# PowerRouting.net
KiCad netlist of a schematic drawn in Altium Designer
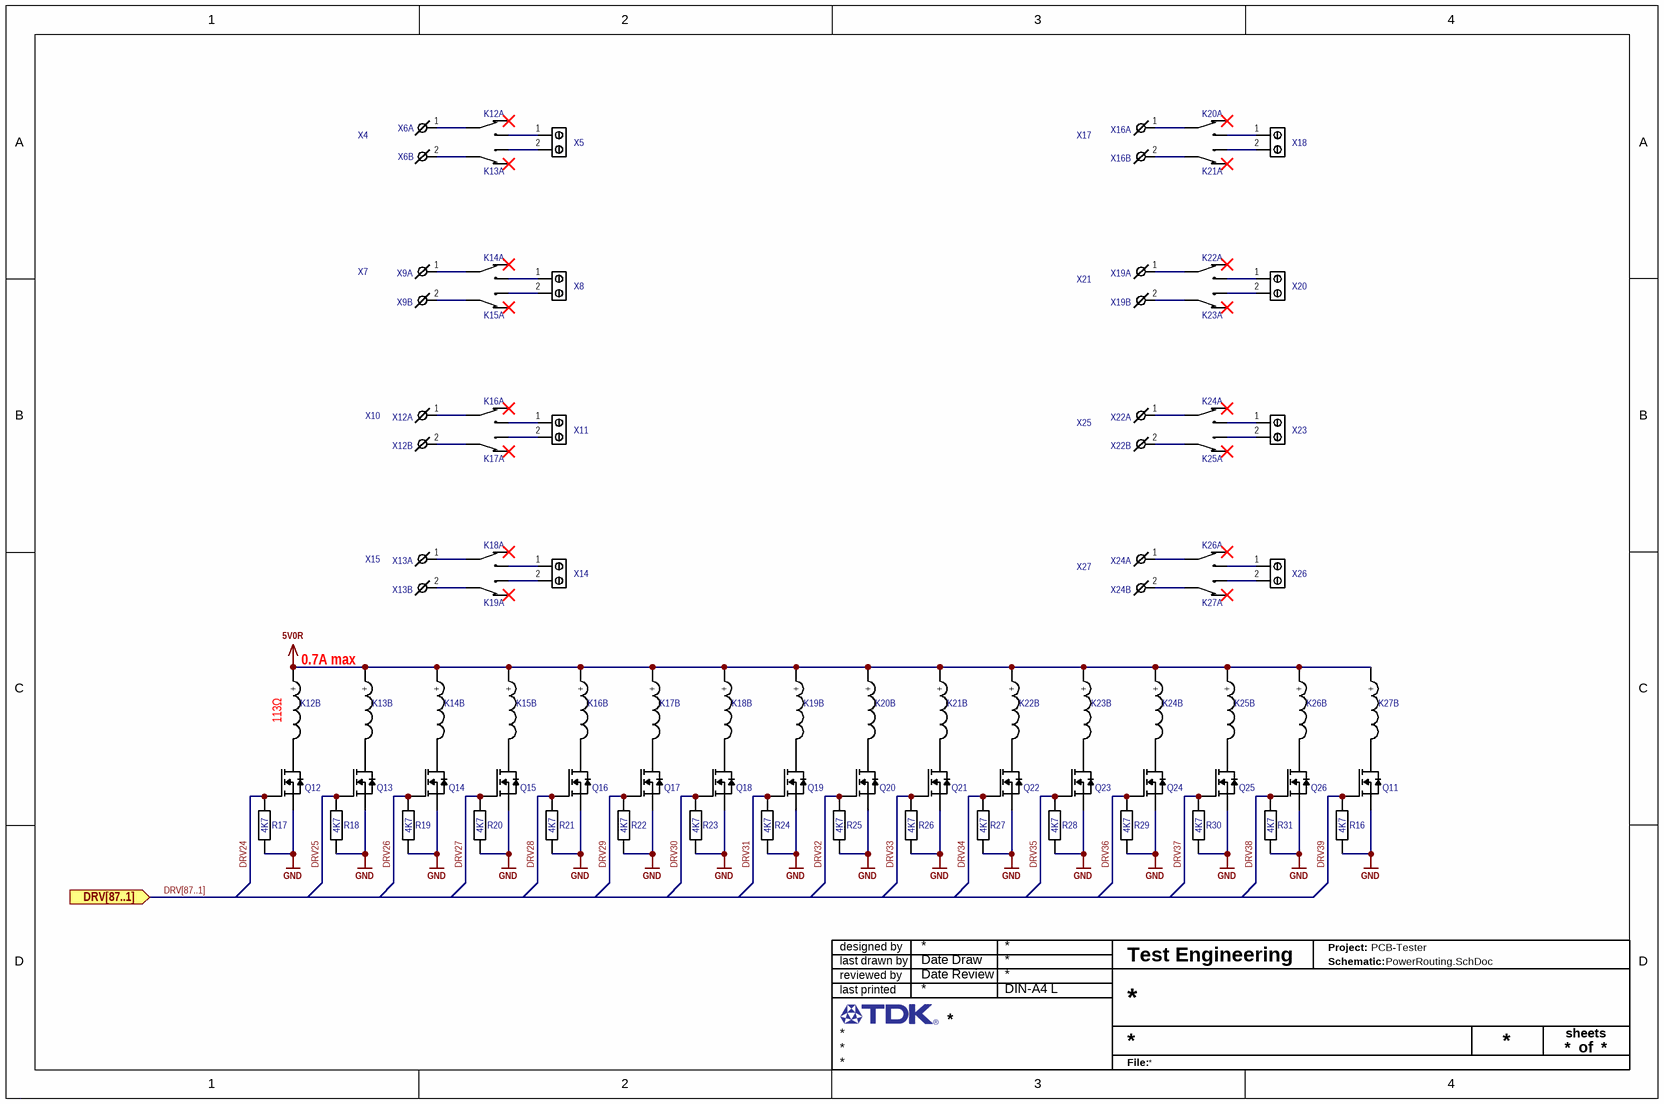
[diagram p0: PowerRouting.SchDoc]

(export (version "E")
  (design (tool "Eeschema 10.0.6"))
  (components
    (comp (ref "K12")
      (value "K")
      (footprint "HF118F005-1ZS1")
      (description "5V Power Relay, switch over")
      (fields
        (field (name "02. DISTRIBUTOR PART NUMBER") "176-2821")
        (field (name "07. MANUFACTURER  PART NUMBER") "HF118F/005-1ZS1T(136)")
        (field (name "COIL RESISTANCE") "113Ω")
        (field (name "13. CREATED DATE/NAME") "AUG2018/Hören")
      )
      (libsource (lib "chickenfood") (part "HF118F005-1ZS1"))
    )
    (comp (ref "K13")
      (value "K")
      (footprint "HF118F005-1ZS1")
      (description "5V Power Relay, switch over")
      (fields
        (field (name "02. DISTRIBUTOR PART NUMBER") "176-2821")
        (field (name "07. MANUFACTURER  PART NUMBER") "HF118F/005-1ZS1T(136)")
        (field (name "13. CREATED DATE/NAME") "AUG2018/Hören")
      )
      (libsource (lib "chickenfood") (part "HF118F005-1ZS1"))
    )
    (comp (ref "K14")
      (value "K")
      (footprint "HF118F005-1ZS1")
      (description "5V Power Relay, switch over")
      (fields
        (field (name "02. DISTRIBUTOR PART NUMBER") "176-2821")
        (field (name "07. MANUFACTURER  PART NUMBER") "HF118F/005-1ZS1T(136)")
        (field (name "13. CREATED DATE/NAME") "AUG2018/Hören")
      )
      (libsource (lib "chickenfood") (part "HF118F005-1ZS1"))
    )
    (comp (ref "K15")
      (value "K")
      (footprint "HF118F005-1ZS1")
      (description "5V Power Relay, switch over")
      (fields
        (field (name "02. DISTRIBUTOR PART NUMBER") "176-2821")
        (field (name "07. MANUFACTURER  PART NUMBER") "HF118F/005-1ZS1T(136)")
        (field (name "13. CREATED DATE/NAME") "AUG2018/Hören")
      )
      (libsource (lib "") (part "HF118F005-1ZS1_1"))
    )
    (comp (ref "K16")
      (value "K")
      (footprint "HF118F005-1ZS1")
      (description "5V Power Relay, switch over")
      (fields
        (field (name "02. DISTRIBUTOR PART NUMBER") "176-2821")
        (field (name "07. MANUFACTURER  PART NUMBER") "HF118F/005-1ZS1T(136)")
        (field (name "13. CREATED DATE/NAME") "AUG2018/Hören")
      )
      (libsource (lib "chickenfood") (part "HF118F005-1ZS1"))
    )
    (comp (ref "K17")
      (value "K")
      (footprint "HF118F005-1ZS1")
      (description "5V Power Relay, switch over")
      (fields
        (field (name "02. DISTRIBUTOR PART NUMBER") "176-2821")
        (field (name "07. MANUFACTURER  PART NUMBER") "HF118F/005-1ZS1T(136)")
        (field (name "13. CREATED DATE/NAME") "AUG2018/Hören")
      )
      (libsource (lib "chickenfood") (part "HF118F005-1ZS1"))
    )
    (comp (ref "K18")
      (value "K")
      (footprint "HF118F005-1ZS1")
      (description "5V Power Relay, switch over")
      (fields
        (field (name "02. DISTRIBUTOR PART NUMBER") "176-2821")
        (field (name "07. MANUFACTURER  PART NUMBER") "HF118F/005-1ZS1T(136)")
        (field (name "13. CREATED DATE/NAME") "AUG2018/Hören")
      )
      (libsource (lib "chickenfood") (part "HF118F005-1ZS1"))
    )
    (comp (ref "K19")
      (value "K")
      (footprint "HF118F005-1ZS1")
      (description "5V Power Relay, switch over")
      (fields
        (field (name "02. DISTRIBUTOR PART NUMBER") "176-2821")
        (field (name "07. MANUFACTURER  PART NUMBER") "HF118F/005-1ZS1T(136)")
        (field (name "13. CREATED DATE/NAME") "AUG2018/Hören")
      )
      (libsource (lib "chickenfood") (part "HF118F005-1ZS1"))
    )
    (comp (ref "K20")
      (value "K")
      (footprint "HF118F005-1ZS1")
      (description "5V Power Relay, switch over")
      (fields
        (field (name "02. DISTRIBUTOR PART NUMBER") "176-2821")
        (field (name "07. MANUFACTURER  PART NUMBER") "HF118F/005-1ZS1T(136)")
        (field (name "13. CREATED DATE/NAME") "AUG2018/Hören")
      )
      (libsource (lib "chickenfood") (part "HF118F005-1ZS1"))
    )
    (comp (ref "K21")
      (value "K")
      (footprint "HF118F005-1ZS1")
      (description "5V Power Relay, switch over")
      (fields
        (field (name "02. DISTRIBUTOR PART NUMBER") "176-2821")
        (field (name "07. MANUFACTURER  PART NUMBER") "HF118F/005-1ZS1T(136)")
        (field (name "13. CREATED DATE/NAME") "AUG2018/Hören")
      )
      (libsource (lib "") (part "HF118F005-1ZS1_1"))
    )
    (comp (ref "K22")
      (value "K")
      (footprint "HF118F005-1ZS1")
      (description "5V Power Relay, switch over")
      (fields
        (field (name "02. DISTRIBUTOR PART NUMBER") "176-2821")
        (field (name "07. MANUFACTURER  PART NUMBER") "HF118F/005-1ZS1T(136)")
        (field (name "13. CREATED DATE/NAME") "AUG2018/Hören")
      )
      (libsource (lib "chickenfood") (part "HF118F005-1ZS1"))
    )
    (comp (ref "K23")
      (value "K")
      (footprint "HF118F005-1ZS1")
      (description "5V Power Relay, switch over")
      (fields
        (field (name "02. DISTRIBUTOR PART NUMBER") "176-2821")
        (field (name "07. MANUFACTURER  PART NUMBER") "HF118F/005-1ZS1T(136)")
        (field (name "13. CREATED DATE/NAME") "AUG2018/Hören")
      )
      (libsource (lib "") (part "HF118F005-1ZS1_1"))
    )
    (comp (ref "K24")
      (value "K")
      (footprint "HF118F005-1ZS1")
      (description "5V Power Relay, switch over")
      (fields
        (field (name "02. DISTRIBUTOR PART NUMBER") "176-2821")
        (field (name "07. MANUFACTURER  PART NUMBER") "HF118F/005-1ZS1T(136)")
        (field (name "13. CREATED DATE/NAME") "AUG2018/Hören")
      )
      (libsource (lib "chickenfood") (part "HF118F005-1ZS1"))
    )
    (comp (ref "K25")
      (value "K")
      (footprint "HF118F005-1ZS1")
      (description "5V Power Relay, switch over")
      (fields
        (field (name "02. DISTRIBUTOR PART NUMBER") "176-2821")
        (field (name "07. MANUFACTURER  PART NUMBER") "HF118F/005-1ZS1T(136)")
        (field (name "13. CREATED DATE/NAME") "AUG2018/Hören")
      )
      (libsource (lib "chickenfood") (part "HF118F005-1ZS1"))
    )
    (comp (ref "K26")
      (value "K")
      (footprint "HF118F005-1ZS1")
      (description "5V Power Relay, switch over")
      (fields
        (field (name "02. DISTRIBUTOR PART NUMBER") "176-2821")
        (field (name "07. MANUFACTURER  PART NUMBER") "HF118F/005-1ZS1T(136)")
        (field (name "13. CREATED DATE/NAME") "AUG2018/Hören")
      )
      (libsource (lib "chickenfood") (part "HF118F005-1ZS1"))
    )
    (comp (ref "K27")
      (value "K")
      (footprint "HF118F005-1ZS1")
      (description "5V Power Relay, switch over")
      (fields
        (field (name "02. DISTRIBUTOR PART NUMBER") "176-2821")
        (field (name "07. MANUFACTURER  PART NUMBER") "HF118F/005-1ZS1T(136)")
        (field (name "13. CREATED DATE/NAME") "AUG2018/Hören")
      )
      (libsource (lib "") (part "HF118F005-1ZS1_1"))
    )
    (comp (ref "Q11")
      (value "Q")
      (footprint "SOT23-3")
      (description "MOSFET N-CH 25V 680MA SOT-23")
      (fields
        (field (name "02. DISTRIBUTOR PART NUMBER") "FDV303NDKR-ND")
        (field (name "07. MANUFACTURER  PART NUMBER") "FDV303N")
        (field (name "13. CREATED DATE/NAME") "AUG 2018 / Hören")
      )
      (libsource (lib "SCT8-Board1") (part "FDV303N"))
    )
    (comp (ref "Q12")
      (value "Q")
      (footprint "SOT23-3")
      (description "MOSFET N-CH 25V 680MA SOT-23")
      (fields
        (field (name "02. DISTRIBUTOR PART NUMBER") "FDV303NDKR-ND")
        (field (name "07. MANUFACTURER  PART NUMBER") "FDV303N")
        (field (name "13. CREATED DATE/NAME") "AUG 2018 / Hören")
      )
      (libsource (lib "SCT8-Board1") (part "FDV303N"))
    )
    (comp (ref "Q13")
      (value "Q")
      (footprint "SOT23-3")
      (description "MOSFET N-CH 25V 680MA SOT-23")
      (fields
        (field (name "02. DISTRIBUTOR PART NUMBER") "FDV303NDKR-ND")
        (field (name "07. MANUFACTURER  PART NUMBER") "FDV303N")
        (field (name "13. CREATED DATE/NAME") "AUG 2018 / Hören")
      )
      (libsource (lib "SCT8-Board1") (part "FDV303N"))
    )
    (comp (ref "Q14")
      (value "Q")
      (footprint "SOT23-3")
      (description "MOSFET N-CH 25V 680MA SOT-23")
      (fields
        (field (name "02. DISTRIBUTOR PART NUMBER") "FDV303NDKR-ND")
        (field (name "07. MANUFACTURER  PART NUMBER") "FDV303N")
        (field (name "13. CREATED DATE/NAME") "AUG 2018 / Hören")
      )
      (libsource (lib "SCT8-Board1") (part "FDV303N"))
    )
    (comp (ref "Q15")
      (value "Q")
      (footprint "SOT23-3")
      (description "MOSFET N-CH 25V 680MA SOT-23")
      (fields
        (field (name "02. DISTRIBUTOR PART NUMBER") "FDV303NDKR-ND")
        (field (name "07. MANUFACTURER  PART NUMBER") "FDV303N")
        (field (name "13. CREATED DATE/NAME") "AUG 2018 / Hören")
      )
      (libsource (lib "SCT8-Board1") (part "FDV303N"))
    )
    (comp (ref "Q16")
      (value "Q")
      (footprint "SOT23-3")
      (description "MOSFET N-CH 25V 680MA SOT-23")
      (fields
        (field (name "02. DISTRIBUTOR PART NUMBER") "FDV303NDKR-ND")
        (field (name "07. MANUFACTURER  PART NUMBER") "FDV303N")
        (field (name "13. CREATED DATE/NAME") "AUG 2018 / Hören")
      )
      (libsource (lib "SCT8-Board1") (part "FDV303N"))
    )
    (comp (ref "Q17")
      (value "Q")
      (footprint "SOT23-3")
      (description "MOSFET N-CH 25V 680MA SOT-23")
      (fields
        (field (name "02. DISTRIBUTOR PART NUMBER") "FDV303NDKR-ND")
        (field (name "07. MANUFACTURER  PART NUMBER") "FDV303N")
        (field (name "13. CREATED DATE/NAME") "AUG 2018 / Hören")
      )
      (libsource (lib "SCT8-Board1") (part "FDV303N"))
    )
    (comp (ref "Q18")
      (value "Q")
      (footprint "SOT23-3")
      (description "MOSFET N-CH 25V 680MA SOT-23")
      (fields
        (field (name "02. DISTRIBUTOR PART NUMBER") "FDV303NDKR-ND")
        (field (name "07. MANUFACTURER  PART NUMBER") "FDV303N")
        (field (name "13. CREATED DATE/NAME") "AUG 2018 / Hören")
      )
      (libsource (lib "SCT8-Board1") (part "FDV303N"))
    )
    (comp (ref "Q19")
      (value "Q")
      (footprint "SOT23-3")
      (description "MOSFET N-CH 25V 680MA SOT-23")
      (fields
        (field (name "02. DISTRIBUTOR PART NUMBER") "FDV303NDKR-ND")
        (field (name "07. MANUFACTURER  PART NUMBER") "FDV303N")
        (field (name "13. CREATED DATE/NAME") "AUG 2018 / Hören")
      )
      (libsource (lib "SCT8-Board1") (part "FDV303N"))
    )
    (comp (ref "Q20")
      (value "Q")
      (footprint "SOT23-3")
      (description "MOSFET N-CH 25V 680MA SOT-23")
      (fields
        (field (name "02. DISTRIBUTOR PART NUMBER") "FDV303NDKR-ND")
        (field (name "07. MANUFACTURER  PART NUMBER") "FDV303N")
        (field (name "13. CREATED DATE/NAME") "AUG 2018 / Hören")
      )
      (libsource (lib "SCT8-Board1") (part "FDV303N"))
    )
    (comp (ref "Q21")
      (value "Q")
      (footprint "SOT23-3")
      (description "MOSFET N-CH 25V 680MA SOT-23")
      (fields
        (field (name "02. DISTRIBUTOR PART NUMBER") "FDV303NDKR-ND")
        (field (name "07. MANUFACTURER  PART NUMBER") "FDV303N")
        (field (name "13. CREATED DATE/NAME") "AUG 2018 / Hören")
      )
      (libsource (lib "SCT8-Board1") (part "FDV303N"))
    )
    (comp (ref "Q22")
      (value "Q")
      (footprint "SOT23-3")
      (description "MOSFET N-CH 25V 680MA SOT-23")
      (fields
        (field (name "02. DISTRIBUTOR PART NUMBER") "FDV303NDKR-ND")
        (field (name "07. MANUFACTURER  PART NUMBER") "FDV303N")
        (field (name "13. CREATED DATE/NAME") "AUG 2018 / Hören")
      )
      (libsource (lib "SCT8-Board1") (part "FDV303N"))
    )
    (comp (ref "Q23")
      (value "Q")
      (footprint "SOT23-3")
      (description "MOSFET N-CH 25V 680MA SOT-23")
      (fields
        (field (name "02. DISTRIBUTOR PART NUMBER") "FDV303NDKR-ND")
        (field (name "07. MANUFACTURER  PART NUMBER") "FDV303N")
        (field (name "13. CREATED DATE/NAME") "AUG 2018 / Hören")
      )
      (libsource (lib "SCT8-Board1") (part "FDV303N"))
    )
    (comp (ref "Q24")
      (value "Q")
      (footprint "SOT23-3")
      (description "MOSFET N-CH 25V 680MA SOT-23")
      (fields
        (field (name "02. DISTRIBUTOR PART NUMBER") "FDV303NDKR-ND")
        (field (name "07. MANUFACTURER  PART NUMBER") "FDV303N")
        (field (name "13. CREATED DATE/NAME") "AUG 2018 / Hören")
      )
      (libsource (lib "SCT8-Board1") (part "FDV303N"))
    )
    (comp (ref "Q25")
      (value "Q")
      (footprint "SOT23-3")
      (description "MOSFET N-CH 25V 680MA SOT-23")
      (fields
        (field (name "02. DISTRIBUTOR PART NUMBER") "FDV303NDKR-ND")
        (field (name "07. MANUFACTURER  PART NUMBER") "FDV303N")
        (field (name "13. CREATED DATE/NAME") "AUG 2018 / Hören")
      )
      (libsource (lib "SCT8-Board1") (part "FDV303N"))
    )
    (comp (ref "Q26")
      (value "Q")
      (footprint "SOT23-3")
      (description "MOSFET N-CH 25V 680MA SOT-23")
      (fields
        (field (name "02. DISTRIBUTOR PART NUMBER") "FDV303NDKR-ND")
        (field (name "07. MANUFACTURER  PART NUMBER") "FDV303N")
        (field (name "13. CREATED DATE/NAME") "AUG 2018 / Hören")
      )
      (libsource (lib "SCT8-Board1") (part "FDV303N"))
    )
    (comp (ref "R16")
      (value "4K7")
      (footprint "R0402 Reflow")
      (description "Resistor")
      (fields
        (field (name "TOLERANCE") "±1%")
        (field (name "Comment") "R")
        (field (name "13. CREATED DATE/NAME") "AUG2018/Hören")
      )
      (libsource (lib "chickenfood") (part "R"))
    )
    (comp (ref "R17")
      (value "4K7")
      (footprint "R0402 Reflow")
      (description "Resistor")
      (fields
        (field (name "TOLERANCE") "±1%")
        (field (name "Comment") "R")
        (field (name "13. CREATED DATE/NAME") "AUG2018/Hören")
      )
      (libsource (lib "chickenfood") (part "R"))
    )
    (comp (ref "R18")
      (value "4K7")
      (footprint "R0402 Reflow")
      (description "Resistor")
      (fields
        (field (name "TOLERANCE") "±1%")
        (field (name "Comment") "R")
        (field (name "13. CREATED DATE/NAME") "AUG2018/Hören")
      )
      (libsource (lib "chickenfood") (part "R"))
    )
    (comp (ref "R19")
      (value "4K7")
      (footprint "R0402 Reflow")
      (description "Resistor")
      (fields
        (field (name "TOLERANCE") "±1%")
        (field (name "Comment") "R")
        (field (name "13. CREATED DATE/NAME") "AUG2018/Hören")
      )
      (libsource (lib "chickenfood") (part "R"))
    )
    (comp (ref "R20")
      (value "4K7")
      (footprint "R0402 Reflow")
      (description "Resistor")
      (fields
        (field (name "TOLERANCE") "±1%")
        (field (name "Comment") "R")
        (field (name "13. CREATED DATE/NAME") "AUG2018/Hören")
      )
      (libsource (lib "chickenfood") (part "R"))
    )
    (comp (ref "R21")
      (value "4K7")
      (footprint "R0402 Reflow")
      (description "Resistor")
      (fields
        (field (name "TOLERANCE") "±1%")
        (field (name "Comment") "R")
        (field (name "13. CREATED DATE/NAME") "AUG2018/Hören")
      )
      (libsource (lib "chickenfood") (part "R"))
    )
    (comp (ref "R22")
      (value "4K7")
      (footprint "R0402 Reflow")
      (description "Resistor")
      (fields
        (field (name "TOLERANCE") "±1%")
        (field (name "Comment") "R")
        (field (name "13. CREATED DATE/NAME") "AUG2018/Hören")
      )
      (libsource (lib "chickenfood") (part "R"))
    )
    (comp (ref "R23")
      (value "4K7")
      (footprint "R0402 Reflow")
      (description "Resistor")
      (fields
        (field (name "TOLERANCE") "±1%")
        (field (name "Comment") "R")
        (field (name "13. CREATED DATE/NAME") "AUG2018/Hören")
      )
      (libsource (lib "chickenfood") (part "R"))
    )
    (comp (ref "R24")
      (value "4K7")
      (footprint "R0402 Reflow")
      (description "Resistor")
      (fields
        (field (name "TOLERANCE") "±1%")
        (field (name "Comment") "R")
        (field (name "13. CREATED DATE/NAME") "AUG2018/Hören")
      )
      (libsource (lib "chickenfood") (part "R"))
    )
    (comp (ref "R25")
      (value "4K7")
      (footprint "R0402 Reflow")
      (description "Resistor")
      (fields
        (field (name "TOLERANCE") "±1%")
        (field (name "Comment") "R")
        (field (name "13. CREATED DATE/NAME") "AUG2018/Hören")
      )
      (libsource (lib "chickenfood") (part "R"))
    )
    (comp (ref "R26")
      (value "4K7")
      (footprint "R0402 Reflow")
      (description "Resistor")
      (fields
        (field (name "TOLERANCE") "±1%")
        (field (name "Comment") "R")
        (field (name "13. CREATED DATE/NAME") "AUG2018/Hören")
      )
      (libsource (lib "chickenfood") (part "R"))
    )
    (comp (ref "R27")
      (value "4K7")
      (footprint "R0402 Reflow")
      (description "Resistor")
      (fields
        (field (name "TOLERANCE") "±1%")
        (field (name "Comment") "R")
        (field (name "13. CREATED DATE/NAME") "AUG2018/Hören")
      )
      (libsource (lib "chickenfood") (part "R"))
    )
    (comp (ref "R28")
      (value "4K7")
      (footprint "R0402 Reflow")
      (description "Resistor")
      (fields
        (field (name "TOLERANCE") "±1%")
        (field (name "Comment") "R")
        (field (name "13. CREATED DATE/NAME") "AUG2018/Hören")
      )
      (libsource (lib "chickenfood") (part "R"))
    )
    (comp (ref "R29")
      (value "4K7")
      (footprint "R0402 Reflow")
      (description "Resistor")
      (fields
        (field (name "TOLERANCE") "±1%")
        (field (name "Comment") "R")
        (field (name "13. CREATED DATE/NAME") "AUG2018/Hören")
      )
      (libsource (lib "chickenfood") (part "R"))
    )
    (comp (ref "R30")
      (value "4K7")
      (footprint "R0402 Reflow")
      (description "Resistor")
      (fields
        (field (name "TOLERANCE") "±1%")
        (field (name "Comment") "R")
        (field (name "13. CREATED DATE/NAME") "AUG2018/Hören")
      )
      (libsource (lib "chickenfood") (part "R"))
    )
    (comp (ref "R31")
      (value "4K7")
      (footprint "R0402 Reflow")
      (description "Resistor")
      (fields
        (field (name "TOLERANCE") "±1%")
        (field (name "Comment") "R")
        (field (name "13. CREATED DATE/NAME") "AUG2018/Hören")
      )
      (libsource (lib "chickenfood") (part "R"))
    )
    (comp (ref "X4")
      (value "X")
      (footprint "691352710002")
      (description "TERM BLOCK PLUG 2POS STR 5MM")
      (fields (field (name "13. CREATED DATE/NAME") "??? / Hören"))
      (libsource (lib "Connectors") (part "691352710002"))
    )
    (comp (ref "X5")
      (value "X")
      (footprint "1731721")
      (description "TERM BLK 2P SIDE ENT 7.62MM PCB")
      (fields
        (field (name "02. DISTRIBUTOR PART NUMBER") "277-5849-ND")
        (field (name "07. MANUFACTURER  PART NUMBER") "1731721")
        (field (name "13. CREATED DATE/NAME") "JAN 2019 / Hören")
      )
      (libsource (lib "Connectors") (part "1731721"))
    )
    (comp (ref "X6")
      (value "X")
      (footprint "691312710002")
      (description "TERM BLOCK HDR 2POS 90DEG 5MM")
      (fields
        (field (name "02. DISTRIBUTOR PART NUMBER") "732-2805-ND")
        (field (name "07. MANUFACTURER  PART NUMBER") "691312710002")
        (field (name "13. CREATED DATE/NAME") "??? / Hören")
      )
      (libsource (lib "Connectors") (part "691312710002"))
    )
    (comp (ref "X7")
      (value "X")
      (footprint "691352710002")
      (description "TERM BLOCK PLUG 2POS STR 5MM")
      (fields (field (name "13. CREATED DATE/NAME") "??? / Hören"))
      (libsource (lib "Connectors") (part "691352710002"))
    )
    (comp (ref "X8")
      (value "X")
      (footprint "1731721")
      (description "TERM BLK 2P SIDE ENT 7.62MM PCB")
      (fields
        (field (name "02. DISTRIBUTOR PART NUMBER") "277-5849-ND")
        (field (name "07. MANUFACTURER  PART NUMBER") "1731721")
        (field (name "13. CREATED DATE/NAME") "JAN 2019 / Hören")
      )
      (libsource (lib "Connectors") (part "1731721"))
    )
    (comp (ref "X9")
      (value "X")
      (footprint "691312710002")
      (description "TERM BLOCK HDR 2POS 90DEG 5MM")
      (fields
        (field (name "02. DISTRIBUTOR PART NUMBER") "732-2805-ND")
        (field (name "07. MANUFACTURER  PART NUMBER") "691312710002")
        (field (name "13. CREATED DATE/NAME") "??? / Hören")
      )
      (libsource (lib "Connectors") (part "691312710002"))
    )
    (comp (ref "X10")
      (value "X")
      (footprint "691352710002")
      (description "TERM BLOCK PLUG 2POS STR 5MM")
      (fields (field (name "13. CREATED DATE/NAME") "??? / Hören"))
      (libsource (lib "Connectors") (part "691352710002"))
    )
    (comp (ref "X11")
      (value "X")
      (footprint "1731721")
      (description "TERM BLK 2P SIDE ENT 7.62MM PCB")
      (fields
        (field (name "02. DISTRIBUTOR PART NUMBER") "277-5849-ND")
        (field (name "07. MANUFACTURER  PART NUMBER") "1731721")
        (field (name "13. CREATED DATE/NAME") "JAN 2019 / Hören")
      )
      (libsource (lib "Connectors") (part "1731721"))
    )
    (comp (ref "X12")
      (value "X")
      (footprint "691312710002")
      (description "TERM BLOCK HDR 2POS 90DEG 5MM")
      (fields
        (field (name "02. DISTRIBUTOR PART NUMBER") "732-2805-ND")
        (field (name "07. MANUFACTURER  PART NUMBER") "691312710002")
        (field (name "13. CREATED DATE/NAME") "??? / Hören")
      )
      (libsource (lib "Connectors") (part "691312710002"))
    )
    (comp (ref "X13")
      (value "X")
      (footprint "691312710002")
      (description "TERM BLOCK HDR 2POS 90DEG 5MM")
      (fields
        (field (name "02. DISTRIBUTOR PART NUMBER") "732-2805-ND")
        (field (name "07. MANUFACTURER  PART NUMBER") "691312710002")
        (field (name "13. CREATED DATE/NAME") "??? / Hören")
      )
      (libsource (lib "Connectors") (part "691312710002"))
    )
    (comp (ref "X14")
      (value "X")
      (footprint "1731721")
      (description "TERM BLK 2P SIDE ENT 7.62MM PCB")
      (fields
        (field (name "02. DISTRIBUTOR PART NUMBER") "277-5849-ND")
        (field (name "07. MANUFACTURER  PART NUMBER") "1731721")
        (field (name "13. CREATED DATE/NAME") "JAN 2019 / Hören")
      )
      (libsource (lib "Connectors") (part "1731721"))
    )
    (comp (ref "X15")
      (value "X")
      (footprint "691352710002")
      (description "TERM BLOCK PLUG 2POS STR 5MM")
      (fields (field (name "13. CREATED DATE/NAME") "??? / Hören"))
      (libsource (lib "Connectors") (part "691352710002"))
    )
    (comp (ref "X16")
      (value "X")
      (footprint "691312710002")
      (description "TERM BLOCK HDR 2POS 90DEG 5MM")
      (fields
        (field (name "02. DISTRIBUTOR PART NUMBER") "732-2805-ND")
        (field (name "07. MANUFACTURER  PART NUMBER") "691312710002")
        (field (name "13. CREATED DATE/NAME") "??? / Hören")
      )
      (libsource (lib "Connectors") (part "691312710002"))
    )
    (comp (ref "X17")
      (value "X")
      (footprint "691352710002")
      (description "TERM BLOCK PLUG 2POS STR 5MM")
      (fields (field (name "13. CREATED DATE/NAME") "??? / Hören"))
      (libsource (lib "Connectors") (part "691352710002"))
    )
    (comp (ref "X18")
      (value "X")
      (footprint "1731721")
      (description "TERM BLK 2P SIDE ENT 7.62MM PCB")
      (fields
        (field (name "02. DISTRIBUTOR PART NUMBER") "277-5849-ND")
        (field (name "07. MANUFACTURER  PART NUMBER") "1731721")
        (field (name "13. CREATED DATE/NAME") "JAN 2019 / Hören")
      )
      (libsource (lib "Connectors") (part "1731721"))
    )
    (comp (ref "X19")
      (value "X")
      (footprint "691312710002")
      (description "TERM BLOCK HDR 2POS 90DEG 5MM")
      (fields
        (field (name "02. DISTRIBUTOR PART NUMBER") "732-2805-ND")
        (field (name "07. MANUFACTURER  PART NUMBER") "691312710002")
        (field (name "13. CREATED DATE/NAME") "??? / Hören")
      )
      (libsource (lib "Connectors") (part "691312710002"))
    )
    (comp (ref "X20")
      (value "X")
      (footprint "1731721")
      (description "TERM BLK 2P SIDE ENT 7.62MM PCB")
      (fields
        (field (name "02. DISTRIBUTOR PART NUMBER") "277-5849-ND")
        (field (name "07. MANUFACTURER  PART NUMBER") "1731721")
        (field (name "13. CREATED DATE/NAME") "JAN 2019 / Hören")
      )
      (libsource (lib "Connectors") (part "1731721"))
    )
    (comp (ref "X21")
      (value "X")
      (footprint "691352710002")
      (description "TERM BLOCK PLUG 2POS STR 5MM")
      (fields (field (name "13. CREATED DATE/NAME") "??? / Hören"))
      (libsource (lib "Connectors") (part "691352710002"))
    )
    (comp (ref "X22")
      (value "X")
      (footprint "691312710002")
      (description "TERM BLOCK HDR 2POS 90DEG 5MM")
      (fields
        (field (name "02. DISTRIBUTOR PART NUMBER") "732-2805-ND")
        (field (name "07. MANUFACTURER  PART NUMBER") "691312710002")
        (field (name "13. CREATED DATE/NAME") "??? / Hören")
      )
      (libsource (lib "Connectors") (part "691312710002"))
    )
    (comp (ref "X23")
      (value "X")
      (footprint "1731721")
      (description "TERM BLK 2P SIDE ENT 7.62MM PCB")
      (fields
        (field (name "02. DISTRIBUTOR PART NUMBER") "277-5849-ND")
        (field (name "07. MANUFACTURER  PART NUMBER") "1731721")
        (field (name "13. CREATED DATE/NAME") "JAN 2019 / Hören")
      )
      (libsource (lib "Connectors") (part "1731721"))
    )
    (comp (ref "X24")
      (value "X")
      (footprint "691312710002")
      (description "TERM BLOCK HDR 2POS 90DEG 5MM")
      (fields
        (field (name "02. DISTRIBUTOR PART NUMBER") "732-2805-ND")
        (field (name "07. MANUFACTURER  PART NUMBER") "691312710002")
        (field (name "13. CREATED DATE/NAME") "??? / Hören")
      )
      (libsource (lib "Connectors") (part "691312710002"))
    )
    (comp (ref "X25")
      (value "X")
      (footprint "691352710002")
      (description "TERM BLOCK PLUG 2POS STR 5MM")
      (fields (field (name "13. CREATED DATE/NAME") "??? / Hören"))
      (libsource (lib "Connectors") (part "691352710002"))
    )
    (comp (ref "X26")
      (value "X")
      (footprint "1731721")
      (description "TERM BLK 2P SIDE ENT 7.62MM PCB")
      (fields
        (field (name "02. DISTRIBUTOR PART NUMBER") "277-5849-ND")
        (field (name "07. MANUFACTURER  PART NUMBER") "1731721")
        (field (name "13. CREATED DATE/NAME") "JAN 2019 / Hören")
      )
      (libsource (lib "Connectors") (part "1731721"))
    )
    (comp (ref "X27")
      (value "X")
      (footprint "691352710002")
      (description "TERM BLOCK PLUG 2POS STR 5MM")
      (fields (field (name "13. CREATED DATE/NAME") "??? / Hören"))
      (libsource (lib "Connectors") (part "691352710002"))
    )
  )
  (nets
    (net (code "72") (name "/DRV24") (class "Default")
      (node (ref "Q12") (pin "1") (pinfunction "G_1") (pintype "passive"))
      (node (ref "R17") (pin "2") (pinfunction "2_2") (pintype "passive"))
    )
    (net (code "73") (name "/DRV25") (class "Default")
      (node (ref "Q13") (pin "1") (pinfunction "G_1") (pintype "passive"))
      (node (ref "R18") (pin "2") (pinfunction "2_2") (pintype "passive"))
    )
    (net (code "74") (name "/DRV26") (class "Default")
      (node (ref "Q14") (pin "1") (pinfunction "G_1") (pintype "passive"))
      (node (ref "R19") (pin "2") (pinfunction "2_2") (pintype "passive"))
    )
    (net (code "75") (name "/DRV27") (class "Default")
      (node (ref "Q15") (pin "1") (pinfunction "G_1") (pintype "passive"))
      (node (ref "R20") (pin "2") (pinfunction "2_2") (pintype "passive"))
    )
    (net (code "76") (name "/DRV28") (class "Default")
      (node (ref "Q16") (pin "1") (pinfunction "G_1") (pintype "passive"))
      (node (ref "R21") (pin "2") (pinfunction "2_2") (pintype "passive"))
    )
    (net (code "77") (name "/DRV29") (class "Default")
      (node (ref "Q17") (pin "1") (pinfunction "G_1") (pintype "passive"))
      (node (ref "R22") (pin "2") (pinfunction "2_2") (pintype "passive"))
    )
    (net (code "78") (name "/DRV30") (class "Default")
      (node (ref "Q18") (pin "1") (pinfunction "G_1") (pintype "passive"))
      (node (ref "R23") (pin "2") (pinfunction "2_2") (pintype "passive"))
    )
    (net (code "79") (name "/DRV31") (class "Default")
      (node (ref "Q19") (pin "1") (pinfunction "G_1") (pintype "passive"))
      (node (ref "R24") (pin "2") (pinfunction "2_2") (pintype "passive"))
    )
    (net (code "80") (name "/DRV32") (class "Default")
      (node (ref "Q20") (pin "1") (pinfunction "G_1") (pintype "passive"))
      (node (ref "R25") (pin "2") (pinfunction "2_2") (pintype "passive"))
    )
    (net (code "81") (name "/DRV33") (class "Default")
      (node (ref "Q21") (pin "1") (pinfunction "G_1") (pintype "passive"))
      (node (ref "R26") (pin "2") (pinfunction "2_2") (pintype "passive"))
    )
    (net (code "82") (name "/DRV34") (class "Default")
      (node (ref "Q22") (pin "1") (pinfunction "G_1") (pintype "passive"))
      (node (ref "R27") (pin "2") (pinfunction "2_2") (pintype "passive"))
    )
    (net (code "83") (name "/DRV35") (class "Default")
      (node (ref "Q23") (pin "1") (pinfunction "G_1") (pintype "passive"))
      (node (ref "R28") (pin "2") (pinfunction "2_2") (pintype "passive"))
    )
    (net (code "84") (name "/DRV36") (class "Default")
      (node (ref "Q24") (pin "1") (pinfunction "G_1") (pintype "passive"))
      (node (ref "R29") (pin "2") (pinfunction "2_2") (pintype "passive"))
    )
    (net (code "85") (name "/DRV37") (class "Default")
      (node (ref "Q25") (pin "1") (pinfunction "G_1") (pintype "passive"))
      (node (ref "R30") (pin "2") (pinfunction "2_2") (pintype "passive"))
    )
    (net (code "86") (name "/DRV38") (class "Default")
      (node (ref "Q26") (pin "1") (pinfunction "G_1") (pintype "passive"))
      (node (ref "R31") (pin "2") (pinfunction "2_2") (pintype "passive"))
    )
    (net (code "87") (name "/DRV39") (class "Default")
      (node (ref "Q11") (pin "1") (pinfunction "G_1") (pintype "passive"))
      (node (ref "R16") (pin "2") (pinfunction "2_2") (pintype "passive"))
    )
    (net (code "89") (name "5V0R") (class "Default")
      (node (ref "K12") (pin "1") (pinfunction "+_1") (pintype "passive"))
      (node (ref "K13") (pin "1") (pinfunction "+_1") (pintype "passive"))
      (node (ref "K14") (pin "1") (pinfunction "+_1") (pintype "passive"))
      (node (ref "K15") (pin "1") (pinfunction "+_1") (pintype "passive"))
      (node (ref "K16") (pin "1") (pinfunction "+_1") (pintype "passive"))
      (node (ref "K17") (pin "1") (pinfunction "+_1") (pintype "passive"))
      (node (ref "K18") (pin "1") (pinfunction "+_1") (pintype "passive"))
      (node (ref "K19") (pin "1") (pinfunction "+_1") (pintype "passive"))
      (node (ref "K20") (pin "1") (pinfunction "+_1") (pintype "passive"))
      (node (ref "K21") (pin "1") (pinfunction "+_1") (pintype "passive"))
      (node (ref "K22") (pin "1") (pinfunction "+_1") (pintype "passive"))
      (node (ref "K23") (pin "1") (pinfunction "+_1") (pintype "passive"))
      (node (ref "K24") (pin "1") (pinfunction "+_1") (pintype "passive"))
      (node (ref "K25") (pin "1") (pinfunction "+_1") (pintype "passive"))
      (node (ref "K26") (pin "1") (pinfunction "+_1") (pintype "passive"))
      (node (ref "K27") (pin "1") (pinfunction "+_1") (pintype "passive"))
    )
    (net (code "90") (name "GND") (class "Default")
      (node (ref "Q11") (pin "2") (pinfunction "S_2") (pintype "passive"))
      (node (ref "Q12") (pin "2") (pinfunction "S_2") (pintype "passive"))
      (node (ref "Q13") (pin "2") (pinfunction "S_2") (pintype "passive"))
      (node (ref "Q14") (pin "2") (pinfunction "S_2") (pintype "passive"))
      (node (ref "Q15") (pin "2") (pinfunction "S_2") (pintype "passive"))
      (node (ref "Q16") (pin "2") (pinfunction "S_2") (pintype "passive"))
      (node (ref "Q17") (pin "2") (pinfunction "S_2") (pintype "passive"))
      (node (ref "Q18") (pin "2") (pinfunction "S_2") (pintype "passive"))
      (node (ref "Q19") (pin "2") (pinfunction "S_2") (pintype "passive"))
      (node (ref "Q20") (pin "2") (pinfunction "S_2") (pintype "passive"))
      (node (ref "Q21") (pin "2") (pinfunction "S_2") (pintype "passive"))
      (node (ref "Q22") (pin "2") (pinfunction "S_2") (pintype "passive"))
      (node (ref "Q23") (pin "2") (pinfunction "S_2") (pintype "passive"))
      (node (ref "Q24") (pin "2") (pinfunction "S_2") (pintype "passive"))
      (node (ref "Q25") (pin "2") (pinfunction "S_2") (pintype "passive"))
      (node (ref "Q26") (pin "2") (pinfunction "S_2") (pintype "passive"))
      (node (ref "R16") (pin "1") (pinfunction "1_1") (pintype "passive"))
      (node (ref "R17") (pin "1") (pinfunction "1_1") (pintype "passive"))
      (node (ref "R18") (pin "1") (pinfunction "1_1") (pintype "passive"))
      (node (ref "R19") (pin "1") (pinfunction "1_1") (pintype "passive"))
      (node (ref "R20") (pin "1") (pinfunction "1_1") (pintype "passive"))
      (node (ref "R21") (pin "1") (pinfunction "1_1") (pintype "passive"))
      (node (ref "R22") (pin "1") (pinfunction "1_1") (pintype "passive"))
      (node (ref "R23") (pin "1") (pinfunction "1_1") (pintype "passive"))
      (node (ref "R24") (pin "1") (pinfunction "1_1") (pintype "passive"))
      (node (ref "R25") (pin "1") (pinfunction "1_1") (pintype "passive"))
      (node (ref "R26") (pin "1") (pinfunction "1_1") (pintype "passive"))
      (node (ref "R27") (pin "1") (pinfunction "1_1") (pintype "passive"))
      (node (ref "R28") (pin "1") (pinfunction "1_1") (pintype "passive"))
      (node (ref "R29") (pin "1") (pinfunction "1_1") (pintype "passive"))
      (node (ref "R30") (pin "1") (pinfunction "1_1") (pintype "passive"))
      (node (ref "R31") (pin "1") (pinfunction "1_1") (pintype "passive"))
    )
    (net (code "91") (name "Net-(K12A-Cin)") (class "Default")
      (node (ref "K12") (pin "2") (pinfunction "Cin_2") (pintype "passive"))
      (node (ref "X6") (pin "1") (pinfunction "+_1") (pintype "passive"))
    )
    (net (code "92") (name "Net-(K12A-Cno)") (class "Default")
      (node (ref "K12") (pin "3") (pinfunction "Cno_3") (pintype "passive"))
      (node (ref "X5") (pin "1") (pinfunction "1_1") (pintype "passive"))
    )
    (net (code "93") (name "Net-(K12B--)") (class "Default")
      (node (ref "K12") (pin "5") (pinfunction "-_5") (pintype "passive"))
      (node (ref "Q12") (pin "3") (pinfunction "D_3") (pintype "passive"))
    )
    (net (code "94") (name "Net-(K13A-Cin)") (class "Default")
      (node (ref "K13") (pin "2") (pinfunction "Cin_2") (pintype "passive"))
      (node (ref "X6") (pin "2") (pinfunction "-_2") (pintype "passive"))
    )
    (net (code "95") (name "Net-(K13A-Cno)") (class "Default")
      (node (ref "K13") (pin "3") (pinfunction "Cno_3") (pintype "passive"))
      (node (ref "X5") (pin "2") (pinfunction "2_2") (pintype "passive"))
    )
    (net (code "96") (name "Net-(K13B--)") (class "Default")
      (node (ref "K13") (pin "5") (pinfunction "-_5") (pintype "passive"))
      (node (ref "Q13") (pin "3") (pinfunction "D_3") (pintype "passive"))
    )
    (net (code "97") (name "Net-(K14A-Cin)") (class "Default")
      (node (ref "K14") (pin "2") (pinfunction "Cin_2") (pintype "passive"))
      (node (ref "X9") (pin "1") (pinfunction "+_1") (pintype "passive"))
    )
    (net (code "98") (name "Net-(K14A-Cno)") (class "Default")
      (node (ref "K14") (pin "3") (pinfunction "Cno_3") (pintype "passive"))
      (node (ref "X8") (pin "1") (pinfunction "1_1") (pintype "passive"))
    )
    (net (code "99") (name "Net-(K14B--)") (class "Default")
      (node (ref "K14") (pin "5") (pinfunction "-_5") (pintype "passive"))
      (node (ref "Q14") (pin "3") (pinfunction "D_3") (pintype "passive"))
    )
    (net (code "100") (name "Net-(K15A-Cin)") (class "Default")
      (node (ref "K15") (pin "2") (pinfunction "Cin_2") (pintype "passive"))
      (node (ref "X9") (pin "2") (pinfunction "-_2") (pintype "passive"))
    )
    (net (code "101") (name "Net-(K15A-Cno)") (class "Default")
      (node (ref "K15") (pin "3") (pinfunction "Cno_3") (pintype "passive"))
      (node (ref "X8") (pin "2") (pinfunction "2_2") (pintype "passive"))
    )
    (net (code "102") (name "Net-(K15B--)") (class "Default")
      (node (ref "K15") (pin "5") (pinfunction "-_5") (pintype "passive"))
      (node (ref "Q15") (pin "3") (pinfunction "D_3") (pintype "passive"))
    )
    (net (code "103") (name "Net-(K16A-Cin)") (class "Default")
      (node (ref "K16") (pin "2") (pinfunction "Cin_2") (pintype "passive"))
      (node (ref "X12") (pin "1") (pinfunction "+_1") (pintype "passive"))
    )
    (net (code "104") (name "Net-(K16A-Cno)") (class "Default")
      (node (ref "K16") (pin "3") (pinfunction "Cno_3") (pintype "passive"))
      (node (ref "X11") (pin "1") (pinfunction "1_1") (pintype "passive"))
    )
    (net (code "105") (name "Net-(K16B--)") (class "Default")
      (node (ref "K16") (pin "5") (pinfunction "-_5") (pintype "passive"))
      (node (ref "Q16") (pin "3") (pinfunction "D_3") (pintype "passive"))
    )
    (net (code "106") (name "Net-(K17A-Cin)") (class "Default")
      (node (ref "K17") (pin "2") (pinfunction "Cin_2") (pintype "passive"))
      (node (ref "X12") (pin "2") (pinfunction "-_2") (pintype "passive"))
    )
    (net (code "107") (name "Net-(K17A-Cno)") (class "Default")
      (node (ref "K17") (pin "3") (pinfunction "Cno_3") (pintype "passive"))
      (node (ref "X11") (pin "2") (pinfunction "2_2") (pintype "passive"))
    )
    (net (code "108") (name "Net-(K17B--)") (class "Default")
      (node (ref "K17") (pin "5") (pinfunction "-_5") (pintype "passive"))
      (node (ref "Q17") (pin "3") (pinfunction "D_3") (pintype "passive"))
    )
    (net (code "109") (name "Net-(K18A-Cin)") (class "Default")
      (node (ref "K18") (pin "2") (pinfunction "Cin_2") (pintype "passive"))
      (node (ref "X13") (pin "1") (pinfunction "+_1") (pintype "passive"))
    )
    (net (code "110") (name "Net-(K18A-Cno)") (class "Default")
      (node (ref "K18") (pin "3") (pinfunction "Cno_3") (pintype "passive"))
      (node (ref "X14") (pin "1") (pinfunction "1_1") (pintype "passive"))
    )
    (net (code "111") (name "Net-(K18B--)") (class "Default")
      (node (ref "K18") (pin "5") (pinfunction "-_5") (pintype "passive"))
      (node (ref "Q18") (pin "3") (pinfunction "D_3") (pintype "passive"))
    )
    (net (code "112") (name "Net-(K19A-Cin)") (class "Default")
      (node (ref "K19") (pin "2") (pinfunction "Cin_2") (pintype "passive"))
      (node (ref "X13") (pin "2") (pinfunction "-_2") (pintype "passive"))
    )
    (net (code "113") (name "Net-(K19A-Cno)") (class "Default")
      (node (ref "K19") (pin "3") (pinfunction "Cno_3") (pintype "passive"))
      (node (ref "X14") (pin "2") (pinfunction "2_2") (pintype "passive"))
    )
    (net (code "114") (name "Net-(K19B--)") (class "Default")
      (node (ref "K19") (pin "5") (pinfunction "-_5") (pintype "passive"))
      (node (ref "Q19") (pin "3") (pinfunction "D_3") (pintype "passive"))
    )
    (net (code "115") (name "Net-(K20A-Cin)") (class "Default")
      (node (ref "K20") (pin "2") (pinfunction "Cin_2") (pintype "passive"))
      (node (ref "X16") (pin "1") (pinfunction "+_1") (pintype "passive"))
    )
    (net (code "116") (name "Net-(K20A-Cno)") (class "Default")
      (node (ref "K20") (pin "3") (pinfunction "Cno_3") (pintype "passive"))
      (node (ref "X18") (pin "1") (pinfunction "1_1") (pintype "passive"))
    )
    (net (code "117") (name "Net-(K20B--)") (class "Default")
      (node (ref "K20") (pin "5") (pinfunction "-_5") (pintype "passive"))
      (node (ref "Q20") (pin "3") (pinfunction "D_3") (pintype "passive"))
    )
    (net (code "118") (name "Net-(K21A-Cin)") (class "Default")
      (node (ref "K21") (pin "2") (pinfunction "Cin_2") (pintype "passive"))
      (node (ref "X16") (pin "2") (pinfunction "-_2") (pintype "passive"))
    )
    (net (code "119") (name "Net-(K21A-Cno)") (class "Default")
      (node (ref "K21") (pin "3") (pinfunction "Cno_3") (pintype "passive"))
      (node (ref "X18") (pin "2") (pinfunction "2_2") (pintype "passive"))
    )
    (net (code "120") (name "Net-(K21B--)") (class "Default")
      (node (ref "K21") (pin "5") (pinfunction "-_5") (pintype "passive"))
      (node (ref "Q21") (pin "3") (pinfunction "D_3") (pintype "passive"))
    )
    (net (code "121") (name "Net-(K22A-Cin)") (class "Default")
      (node (ref "K22") (pin "2") (pinfunction "Cin_2") (pintype "passive"))
      (node (ref "X19") (pin "1") (pinfunction "+_1") (pintype "passive"))
    )
    (net (code "122") (name "Net-(K22A-Cno)") (class "Default")
      (node (ref "K22") (pin "3") (pinfunction "Cno_3") (pintype "passive"))
      (node (ref "X20") (pin "1") (pinfunction "1_1") (pintype "passive"))
    )
    (net (code "123") (name "Net-(K22B--)") (class "Default")
      (node (ref "K22") (pin "5") (pinfunction "-_5") (pintype "passive"))
      (node (ref "Q22") (pin "3") (pinfunction "D_3") (pintype "passive"))
    )
    (net (code "124") (name "Net-(K23A-Cin)") (class "Default")
      (node (ref "K23") (pin "2") (pinfunction "Cin_2") (pintype "passive"))
      (node (ref "X19") (pin "2") (pinfunction "-_2") (pintype "passive"))
    )
    (net (code "125") (name "Net-(K23A-Cno)") (class "Default")
      (node (ref "K23") (pin "3") (pinfunction "Cno_3") (pintype "passive"))
      (node (ref "X20") (pin "2") (pinfunction "2_2") (pintype "passive"))
    )
    (net (code "126") (name "Net-(K23B--)") (class "Default")
      (node (ref "K23") (pin "5") (pinfunction "-_5") (pintype "passive"))
      (node (ref "Q23") (pin "3") (pinfunction "D_3") (pintype "passive"))
    )
    (net (code "127") (name "Net-(K24A-Cin)") (class "Default")
      (node (ref "K24") (pin "2") (pinfunction "Cin_2") (pintype "passive"))
      (node (ref "X22") (pin "1") (pinfunction "+_1") (pintype "passive"))
    )
    (net (code "128") (name "Net-(K24A-Cno)") (class "Default")
      (node (ref "K24") (pin "3") (pinfunction "Cno_3") (pintype "passive"))
      (node (ref "X23") (pin "1") (pinfunction "1_1") (pintype "passive"))
    )
    (net (code "129") (name "Net-(K24B--)") (class "Default")
      (node (ref "K24") (pin "5") (pinfunction "-_5") (pintype "passive"))
      (node (ref "Q24") (pin "3") (pinfunction "D_3") (pintype "passive"))
    )
    (net (code "130") (name "Net-(K25A-Cin)") (class "Default")
      (node (ref "K25") (pin "2") (pinfunction "Cin_2") (pintype "passive"))
      (node (ref "X22") (pin "2") (pinfunction "-_2") (pintype "passive"))
    )
    (net (code "131") (name "Net-(K25A-Cno)") (class "Default")
      (node (ref "K25") (pin "3") (pinfunction "Cno_3") (pintype "passive"))
      (node (ref "X23") (pin "2") (pinfunction "2_2") (pintype "passive"))
    )
    (net (code "132") (name "Net-(K25B--)") (class "Default")
      (node (ref "K25") (pin "5") (pinfunction "-_5") (pintype "passive"))
      (node (ref "Q25") (pin "3") (pinfunction "D_3") (pintype "passive"))
    )
    (net (code "133") (name "Net-(K26A-Cin)") (class "Default")
      (node (ref "K26") (pin "2") (pinfunction "Cin_2") (pintype "passive"))
      (node (ref "X24") (pin "1") (pinfunction "+_1") (pintype "passive"))
    )
    (net (code "134") (name "Net-(K26A-Cno)") (class "Default")
      (node (ref "K26") (pin "3") (pinfunction "Cno_3") (pintype "passive"))
      (node (ref "X26") (pin "1") (pinfunction "1_1") (pintype "passive"))
    )
    (net (code "135") (name "Net-(K26B--)") (class "Default")
      (node (ref "K26") (pin "5") (pinfunction "-_5") (pintype "passive"))
      (node (ref "Q26") (pin "3") (pinfunction "D_3") (pintype "passive"))
    )
    (net (code "136") (name "Net-(K27A-Cin)") (class "Default")
      (node (ref "K27") (pin "2") (pinfunction "Cin_2") (pintype "passive"))
      (node (ref "X24") (pin "2") (pinfunction "-_2") (pintype "passive"))
    )
    (net (code "137") (name "Net-(K27A-Cno)") (class "Default")
      (node (ref "K27") (pin "3") (pinfunction "Cno_3") (pintype "passive"))
      (node (ref "X26") (pin "2") (pinfunction "2_2") (pintype "passive"))
    )
    (net (code "138") (name "Net-(K27B--)") (class "Default")
      (node (ref "K27") (pin "5") (pinfunction "-_5") (pintype "passive"))
      (node (ref "Q11") (pin "3") (pinfunction "D_3") (pintype "passive"))
    )
    (net (code "139") (name "unconnected-(K12A-Cnc-Pad4)") (class "Default")
      (node (ref "K12") (pin "4") (pinfunction "Cnc_4") (pintype "passive+no_connect"))
    )
    (net (code "140") (name "unconnected-(K13A-Cnc-Pad4)") (class "Default")
      (node (ref "K13") (pin "4") (pinfunction "Cnc_4") (pintype "passive+no_connect"))
    )
    (net (code "141") (name "unconnected-(K14A-Cnc-Pad4)") (class "Default")
      (node (ref "K14") (pin "4") (pinfunction "Cnc_4") (pintype "passive+no_connect"))
    )
    (net (code "142") (name "unconnected-(K15A-Cnc-Pad4)") (class "Default")
      (node (ref "K15") (pin "4") (pinfunction "Cnc_4") (pintype "passive+no_connect"))
    )
    (net (code "143") (name "unconnected-(K16A-Cnc-Pad4)") (class "Default")
      (node (ref "K16") (pin "4") (pinfunction "Cnc_4") (pintype "passive+no_connect"))
    )
    (net (code "144") (name "unconnected-(K17A-Cnc-Pad4)") (class "Default")
      (node (ref "K17") (pin "4") (pinfunction "Cnc_4") (pintype "passive+no_connect"))
    )
    (net (code "145") (name "unconnected-(K18A-Cnc-Pad4)") (class "Default")
      (node (ref "K18") (pin "4") (pinfunction "Cnc_4") (pintype "passive+no_connect"))
    )
    (net (code "146") (name "unconnected-(K19A-Cnc-Pad4)") (class "Default")
      (node (ref "K19") (pin "4") (pinfunction "Cnc_4") (pintype "passive+no_connect"))
    )
    (net (code "147") (name "unconnected-(K20A-Cnc-Pad4)") (class "Default")
      (node (ref "K20") (pin "4") (pinfunction "Cnc_4") (pintype "passive+no_connect"))
    )
    (net (code "148") (name "unconnected-(K21A-Cnc-Pad4)") (class "Default")
      (node (ref "K21") (pin "4") (pinfunction "Cnc_4") (pintype "passive+no_connect"))
    )
    (net (code "149") (name "unconnected-(K22A-Cnc-Pad4)") (class "Default")
      (node (ref "K22") (pin "4") (pinfunction "Cnc_4") (pintype "passive+no_connect"))
    )
    (net (code "150") (name "unconnected-(K23A-Cnc-Pad4)") (class "Default")
      (node (ref "K23") (pin "4") (pinfunction "Cnc_4") (pintype "passive+no_connect"))
    )
    (net (code "151") (name "unconnected-(K24A-Cnc-Pad4)") (class "Default")
      (node (ref "K24") (pin "4") (pinfunction "Cnc_4") (pintype "passive+no_connect"))
    )
    (net (code "152") (name "unconnected-(K25A-Cnc-Pad4)") (class "Default")
      (node (ref "K25") (pin "4") (pinfunction "Cnc_4") (pintype "passive+no_connect"))
    )
    (net (code "153") (name "unconnected-(K26A-Cnc-Pad4)") (class "Default")
      (node (ref "K26") (pin "4") (pinfunction "Cnc_4") (pintype "passive+no_connect"))
    )
    (net (code "154") (name "unconnected-(K27A-Cnc-Pad4)") (class "Default")
      (node (ref "K27") (pin "4") (pinfunction "Cnc_4") (pintype "passive+no_connect"))
    )
  )
)
